# SD.net
KiCad netlist of a schematic drawn in Altium Designer
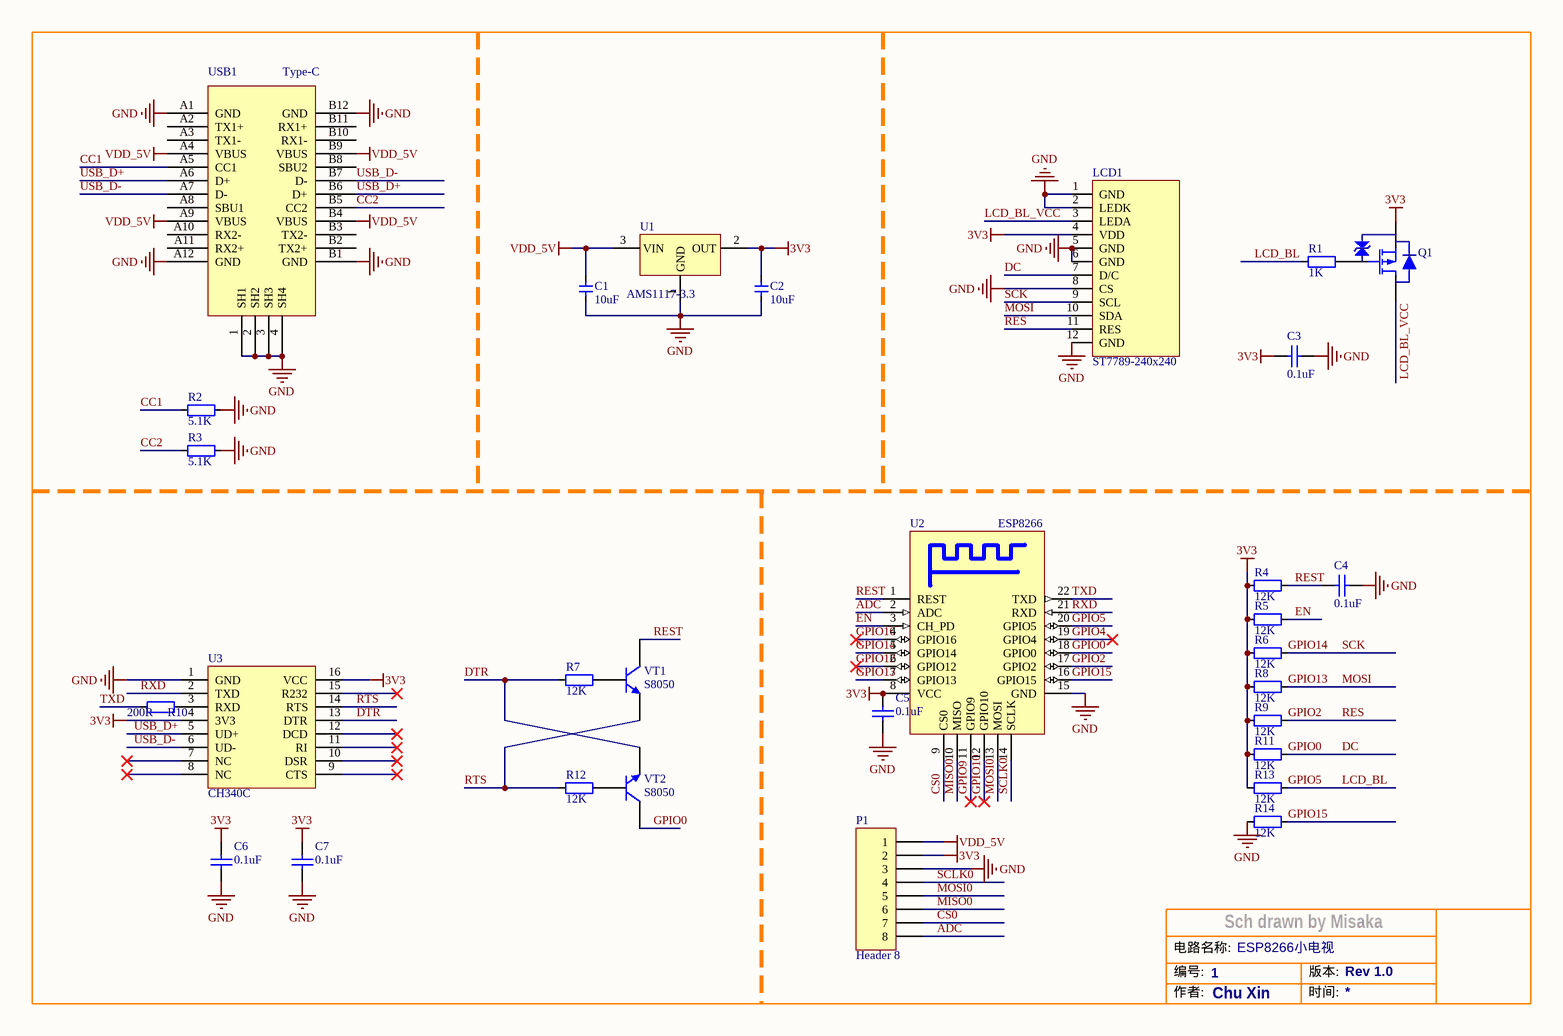
[diagram p0: SD²原理图.SchDoc]

(export (version "E")
  (design (tool "Eeschema 10.0.6"))
  (components
    (comp (ref "C1")
      (value "10uF")
      (footprint "C_0603")
      (description "Capacitor")
      (libsource (lib "MyPcbLib") (part "电容-0402"))
    )
    (comp (ref "C2")
      (value "10uF")
      (footprint "C_0603")
      (description "Capacitor")
      (libsource (lib "MyPcbLib") (part "电容-0402"))
    )
    (comp (ref "C3")
      (value "0.1uF")
      (footprint "C_0603")
      (description "Capacitor")
      (fields (field (name "PUBLISHER") "Altium Limited"))
      (libsource (lib "Miscellaneous Devices") (part "Cap"))
    )
    (comp (ref "C4")
      (value "0.1uF")
      (footprint "C_0603")
      (description "Capacitor")
      (fields (field (name "PUBLISHER") "Altium Limited"))
      (libsource (lib "Miscellaneous Devices") (part "Cap"))
    )
    (comp (ref "C5")
      (value "0.1uF")
      (footprint "C_0603")
      (description "Capacitor")
      (fields (field (name "PUBLISHER") "Altium Limited"))
      (libsource (lib "Miscellaneous Devices") (part "Cap"))
    )
    (comp (ref "C6")
      (value "0.1uF")
      (footprint "C_0603")
      (description "Capacitor")
      (fields (field (name "PUBLISHER") "Altium Limited"))
      (libsource (lib "Miscellaneous Devices") (part "Cap"))
    )
    (comp (ref "C7")
      (value "0.1uF")
      (footprint "C_0603")
      (description "Capacitor")
      (fields (field (name "PUBLISHER") "Altium Limited"))
      (libsource (lib "Miscellaneous Devices") (part "Cap"))
    )
    (comp (ref "LCD1")
      (value "ST7789-240x240")
      (footprint "LCD-240X240-12P")
      (description "显示屏")
      (libsource (lib "mLib") (part "LCD-240x240"))
    )
    (comp (ref "P1")
      (value "Header 8")
      (footprint "FFC_0.5_8")
      (description "Header, 8-Pin")
      (fields (field (name "PUBLISHER") "Altium Limited"))
      (libsource (lib "Miscellaneous Connectors") (part "Header 8"))
    )
    (comp (ref "Q1")
      (value "AO3415A")
      (footprint "SOT-23-y")
      (description "MOSFET")
      (fields (field (name "PUBLISHER") "Altium Limited"))
      (libsource (lib "MyPcbLib") (part "AO3415A"))
    )
    (comp (ref "R1")
      (value "1K")
      (footprint "R_0603")
      (description "Resistor")
      (libsource (lib "") (part "电阻-0402_1"))
    )
    (comp (ref "R2")
      (value "5.1K")
      (footprint "R_0603")
      (description "Resistor")
      (libsource (lib "MyPcbLib") (part "电阻-0402"))
    )
    (comp (ref "R3")
      (value "5.1K")
      (footprint "R_0603")
      (description "Resistor")
      (libsource (lib "MyPcbLib") (part "电阻-0402"))
    )
    (comp (ref "R4")
      (value "12K")
      (footprint "R_0603")
      (description "Resistor")
      (libsource (lib "MyPcbLib") (part "电阻-0402"))
    )
    (comp (ref "R5")
      (value "12K")
      (footprint "R_0603")
      (description "Resistor")
      (libsource (lib "MyPcbLib") (part "电阻-0402"))
    )
    (comp (ref "R6")
      (value "12K")
      (footprint "R_0603")
      (description "Resistor")
      (libsource (lib "MyPcbLib") (part "电阻-0402"))
    )
    (comp (ref "R7")
      (value "12K")
      (footprint "R_0603")
      (description "Resistor")
      (libsource (lib "MyPcbLib") (part "电阻-0402"))
    )
    (comp (ref "R8")
      (value "12K")
      (footprint "R_0603")
      (description "Resistor")
      (libsource (lib "MyPcbLib") (part "电阻-0402"))
    )
    (comp (ref "R9")
      (value "12K")
      (footprint "R_0603")
      (description "Resistor")
      (libsource (lib "MyPcbLib") (part "电阻-0402"))
    )
    (comp (ref "R10")
      (value "200R")
      (footprint "R_0603")
      (description "Resistor")
      (libsource (lib "") (part "电阻-0402_2"))
    )
    (comp (ref "R11")
      (value "12K")
      (footprint "R_0603")
      (description "Resistor")
      (libsource (lib "MyPcbLib") (part "电阻-0402"))
    )
    (comp (ref "R12")
      (value "12K")
      (footprint "R_0603")
      (description "Resistor")
      (libsource (lib "MyPcbLib") (part "电阻-0402"))
    )
    (comp (ref "R13")
      (value "12K")
      (footprint "R_0603")
      (description "Resistor")
      (libsource (lib "MyPcbLib") (part "电阻-0402"))
    )
    (comp (ref "R14")
      (value "12K")
      (footprint "R_0603")
      (description "Resistor")
      (libsource (lib "MyPcbLib") (part "电阻-0402"))
    )
    (comp (ref "U1") (value "AMS1117-3.3") (footprint "SOT223_y") (libsource (lib "数控电源") (part "LM317M")))
    (comp (ref "U2") (value "ESP8266") (footprint "8266") (libsource (lib "Misaka") (part "ESP8266")))
    (comp (ref "U3") (value "CH340C") (footprint "SOP16N_N") (libsource (lib "Misaka") (part "CH340C")))
    (comp (ref "USB1")
      (value "Type-C")
      (footprint "Misaka:Type-C-TOP")
      (libsource (lib "MyPcbLib") (part "USB-Type-C-TOP"))
    )
    (comp (ref "VT1")
      (value "S8050")
      (footprint "SOT-23-y")
      (description "Surface mount NPN transistor, package SOT-23")
      (libsource (lib "MyPcbLib") (part "SMT_TRIODE_NPN"))
    )
    (comp (ref "VT2")
      (value "S8050")
      (footprint "SOT-23-y")
      (description "Surface mount NPN transistor, package SOT-23")
      (libsource (lib "MyPcbLib") (part "SMT_TRIODE_NPN"))
    )
  )
  (nets
    (net (code "1") (name "/ADC") (class "Default")
      (node (ref "P1") (pin "8") (pinfunction "8_8") (pintype "passive"))
      (node (ref "U2") (pin "2") (pinfunction "ADC_2") (pintype "input"))
    )
    (net (code "2") (name "/CC1") (class "Default")
      (node (ref "R2") (pin "1") (pinfunction "1_1") (pintype "passive"))
      (node (ref "USB1") (pin "A5") (pinfunction "CC1_A5") (pintype "passive"))
    )
    (net (code "3") (name "/CC2") (class "Default")
      (node (ref "R3") (pin "1") (pinfunction "1_1") (pintype "passive"))
      (node (ref "USB1") (pin "B5") (pinfunction "CC2_B5") (pintype "passive"))
    )
    (net (code "4") (name "/CS0") (class "Default")
      (node (ref "P1") (pin "7") (pinfunction "7_7") (pintype "passive"))
      (node (ref "U2") (pin "9") (pinfunction "CS0_9") (pintype "passive"))
    )
    (net (code "5") (name "/DC") (class "Default")
      (node (ref "LCD1") (pin "7") (pinfunction "D/C_7") (pintype "passive"))
      (node (ref "R11") (pin "2") (pinfunction "2_2") (pintype "passive"))
      (node (ref "U2") (pin "18") (pinfunction "GPIO0_18") (pintype "bidirectional"))
      (node (ref "VT2") (pin "3") (pinfunction "C_3") (pintype "passive"))
    )
    (net (code "6") (name "/DTR") (class "Default")
      (node (ref "R7") (pin "1") (pinfunction "1_1") (pintype "passive"))
      (node (ref "U3") (pin "13") (pinfunction "DTR_13") (pintype "passive"))
      (node (ref "VT2") (pin "2") (pinfunction "E_2") (pintype "passive"))
    )
    (net (code "7") (name "/EN") (class "Default")
      (node (ref "R5") (pin "2") (pinfunction "2_2") (pintype "passive"))
      (node (ref "U2") (pin "3") (pinfunction "CH_PD_3") (pintype "input"))
    )
    (net (code "8") (name "/GPIO2") (class "Default")
      (node (ref "LCD1") (pin "11") (pinfunction "RES_11") (pintype "passive"))
      (node (ref "R9") (pin "2") (pinfunction "2_2") (pintype "passive"))
      (node (ref "U2") (pin "17") (pinfunction "GPIO2_17") (pintype "bidirectional"))
    )
    (net (code "9") (name "/GPIO4") (class "Default")
      (node (ref "U2") (pin "19") (pinfunction "GPIO4_19") (pintype "bidirectional+no_connect"))
    )
    (net (code "10") (name "/GPIO5") (class "Default")
      (node (ref "R1") (pin "1") (pinfunction "1_1") (pintype "passive"))
      (node (ref "R13") (pin "2") (pinfunction "2_2") (pintype "passive"))
      (node (ref "U2") (pin "20") (pinfunction "GPIO5_20") (pintype "bidirectional"))
    )
    (net (code "11") (name "/GPIO9") (class "Default")
      (node (ref "U2") (pin "11") (pinfunction "GPIO9_11") (pintype "passive+no_connect"))
    )
    (net (code "12") (name "/GPIO10") (class "Default")
      (node (ref "U2") (pin "12") (pinfunction "GPIO10_12") (pintype "passive+no_connect"))
    )
    (net (code "13") (name "/GPIO12") (class "Default")
      (node (ref "U2") (pin "6") (pinfunction "GPIO12_6") (pintype "bidirectional+no_connect"))
    )
    (net (code "14") (name "/GPIO13") (class "Default")
      (node (ref "LCD1") (pin "10") (pinfunction "SDA_10") (pintype "passive"))
      (node (ref "R8") (pin "2") (pinfunction "2_2") (pintype "passive"))
      (node (ref "U2") (pin "7") (pinfunction "GPIO13_7") (pintype "bidirectional"))
    )
    (net (code "15") (name "/GPIO14") (class "Default")
      (node (ref "LCD1") (pin "9") (pinfunction "SCL_9") (pintype "passive"))
      (node (ref "R6") (pin "2") (pinfunction "2_2") (pintype "passive"))
      (node (ref "U2") (pin "5") (pinfunction "GPIO14_5") (pintype "bidirectional"))
    )
    (net (code "16") (name "/GPIO15") (class "Default")
      (node (ref "R14") (pin "2") (pinfunction "2_2") (pintype "passive"))
      (node (ref "U2") (pin "16") (pinfunction "GPIO15_16") (pintype "bidirectional"))
    )
    (net (code "17") (name "/GPIO16") (class "Default")
      (node (ref "U2") (pin "4") (pinfunction "GPIO16_4") (pintype "bidirectional+no_connect"))
    )
    (net (code "18") (name "/LCD_BL_VCC") (class "Default")
      (node (ref "LCD1") (pin "3") (pinfunction "LEDA_3") (pintype "passive"))
      (node (ref "Q1") (pin "3") (pinfunction "D_3") (pintype "passive"))
    )
    (net (code "19") (name "/MISO0") (class "Default")
      (node (ref "P1") (pin "6") (pinfunction "6_6") (pintype "passive"))
      (node (ref "U2") (pin "10") (pinfunction "MISO_10") (pintype "passive"))
    )
    (net (code "20") (name "/MOSI0") (class "Default")
      (node (ref "P1") (pin "5") (pinfunction "5_5") (pintype "passive"))
      (node (ref "U2") (pin "13") (pinfunction "MOSI_13") (pintype "passive"))
    )
    (net (code "21") (name "/REST") (class "Default")
      (node (ref "C4") (pin "2") (pinfunction "2_2") (pintype "passive"))
      (node (ref "R4") (pin "2") (pinfunction "2_2") (pintype "passive"))
      (node (ref "U2") (pin "1") (pinfunction "REST_1") (pintype "passive"))
      (node (ref "VT1") (pin "3") (pinfunction "C_3") (pintype "passive"))
    )
    (net (code "22") (name "/RTS") (class "Default")
      (node (ref "R12") (pin "1") (pinfunction "1_1") (pintype "passive"))
      (node (ref "U3") (pin "14") (pinfunction "RTS_14") (pintype "passive"))
      (node (ref "VT1") (pin "2") (pinfunction "E_2") (pintype "passive"))
    )
    (net (code "23") (name "/RXD") (class "Default")
      (node (ref "U2") (pin "21") (pinfunction "RXD_21") (pintype "input"))
      (node (ref "U3") (pin "2") (pinfunction "TXD_2") (pintype "passive"))
    )
    (net (code "24") (name "/SCLK0") (class "Default")
      (node (ref "P1") (pin "4") (pinfunction "4_4") (pintype "passive"))
      (node (ref "U2") (pin "14") (pinfunction "SCLK_14") (pintype "passive"))
    )
    (net (code "25") (name "/TXD") (class "Default")
      (node (ref "R10") (pin "2") (pinfunction "2_2") (pintype "passive"))
      (node (ref "U2") (pin "22") (pinfunction "TXD_22") (pintype "output"))
    )
    (net (code "26") (name "/USB_D+") (class "Default")
      (node (ref "U3") (pin "5") (pinfunction "UD+_5") (pintype "passive"))
      (node (ref "USB1") (pin "A6") (pinfunction "D+_A6") (pintype "passive"))
      (node (ref "USB1") (pin "B6") (pinfunction "D+_B6") (pintype "passive"))
    )
    (net (code "27") (name "/USB_D-") (class "Default")
      (node (ref "U3") (pin "6") (pinfunction "UD-_6") (pintype "passive"))
      (node (ref "USB1") (pin "A7") (pinfunction "D-_A7") (pintype "passive"))
      (node (ref "USB1") (pin "B7") (pinfunction "D-_B7") (pintype "passive"))
    )
    (net (code "28") (name "3V3") (class "Default")
      (node (ref "C2") (pin "2") (pinfunction "2_2") (pintype "passive"))
      (node (ref "C3") (pin "2") (pinfunction "2_2") (pintype "passive"))
      (node (ref "C5") (pin "2") (pinfunction "2_2") (pintype "passive"))
      (node (ref "C6") (pin "2") (pinfunction "2_2") (pintype "passive"))
      (node (ref "C7") (pin "2") (pinfunction "2_2") (pintype "passive"))
      (node (ref "LCD1") (pin "4") (pinfunction "VDD_4") (pintype "passive"))
      (node (ref "P1") (pin "2") (pinfunction "2_2") (pintype "passive"))
      (node (ref "Q1") (pin "2") (pinfunction "S_2") (pintype "passive"))
      (node (ref "R11") (pin "1") (pinfunction "1_1") (pintype "passive"))
      (node (ref "R13") (pin "1") (pinfunction "1_1") (pintype "passive"))
      (node (ref "R4") (pin "1") (pinfunction "1_1") (pintype "passive"))
      (node (ref "R5") (pin "1") (pinfunction "1_1") (pintype "passive"))
      (node (ref "R6") (pin "1") (pinfunction "1_1") (pintype "passive"))
      (node (ref "R8") (pin "1") (pinfunction "1_1") (pintype "passive"))
      (node (ref "R9") (pin "1") (pinfunction "1_1") (pintype "passive"))
      (node (ref "U1") (pin "2") (pinfunction "OUT_2") (pintype "passive"))
      (node (ref "U2") (pin "8") (pinfunction "VCC_8") (pintype "power_in"))
      (node (ref "U3") (pin "16") (pinfunction "VCC_16") (pintype "passive"))
      (node (ref "U3") (pin "4") (pinfunction "3V3_4") (pintype "passive"))
    )
    (net (code "29") (name "GND") (class "Default")
      (node (ref "C1") (pin "1") (pinfunction "1_1") (pintype "passive"))
      (node (ref "C2") (pin "1") (pinfunction "1_1") (pintype "passive"))
      (node (ref "C3") (pin "1") (pinfunction "1_1") (pintype "passive"))
      (node (ref "C4") (pin "1") (pinfunction "1_1") (pintype "passive"))
      (node (ref "C5") (pin "1") (pinfunction "1_1") (pintype "passive"))
      (node (ref "C6") (pin "1") (pinfunction "1_1") (pintype "passive"))
      (node (ref "C7") (pin "1") (pinfunction "1_1") (pintype "passive"))
      (node (ref "LCD1") (pin "1") (pinfunction "GND_1") (pintype "passive"))
      (node (ref "LCD1") (pin "12") (pinfunction "GND_12") (pintype "passive"))
      (node (ref "LCD1") (pin "2") (pinfunction "LEDK_2") (pintype "passive"))
      (node (ref "LCD1") (pin "5") (pinfunction "GND_5") (pintype "passive"))
      (node (ref "LCD1") (pin "6") (pinfunction "GND_6") (pintype "passive"))
      (node (ref "LCD1") (pin "8") (pinfunction "CS_8") (pintype "passive"))
      (node (ref "P1") (pin "3") (pinfunction "3_3") (pintype "passive"))
      (node (ref "R14") (pin "1") (pinfunction "1_1") (pintype "passive"))
      (node (ref "R2") (pin "2") (pinfunction "2_2") (pintype "passive"))
      (node (ref "R3") (pin "2") (pinfunction "2_2") (pintype "passive"))
      (node (ref "U1") (pin "1") (pinfunction "GND_1") (pintype "passive"))
      (node (ref "U2") (pin "15") (pinfunction "GND_15") (pintype "power_in"))
      (node (ref "U3") (pin "1") (pinfunction "GND_1") (pintype "passive"))
      (node (ref "USB1") (pin "1") (pinfunction "SH1_1") (pintype "passive"))
      (node (ref "USB1") (pin "2") (pinfunction "SH2_2") (pintype "passive"))
      (node (ref "USB1") (pin "3") (pinfunction "SH3_3") (pintype "passive"))
      (node (ref "USB1") (pin "4") (pinfunction "SH4_4") (pintype "passive"))
      (node (ref "USB1") (pin "A1") (pinfunction "GND_A1") (pintype "passive"))
      (node (ref "USB1") (pin "A12") (pinfunction "GND_A12") (pintype "passive"))
      (node (ref "USB1") (pin "B1") (pinfunction "GND_B1") (pintype "passive"))
      (node (ref "USB1") (pin "B12") (pinfunction "GND_B12") (pintype "passive"))
    )
    (net (code "30") (name "Net-(Q1-G)") (class "Default")
      (node (ref "Q1") (pin "1") (pinfunction "G_1") (pintype "passive"))
      (node (ref "R1") (pin "2") (pinfunction "2_2") (pintype "passive"))
    )
    (net (code "31") (name "Net-(U3-RXD)") (class "Default")
      (node (ref "R10") (pin "1") (pinfunction "1_1") (pintype "passive"))
      (node (ref "U3") (pin "3") (pinfunction "RXD_3") (pintype "passive"))
    )
    (net (code "32") (name "Net-(VT1-B)") (class "Default")
      (node (ref "R7") (pin "2") (pinfunction "2_2") (pintype "passive"))
      (node (ref "VT1") (pin "1") (pinfunction "B_1") (pintype "passive"))
    )
    (net (code "33") (name "Net-(VT2-B)") (class "Default")
      (node (ref "R12") (pin "2") (pinfunction "2_2") (pintype "passive"))
      (node (ref "VT2") (pin "1") (pinfunction "B_1") (pintype "passive"))
    )
    (net (code "34") (name "VDD_5V") (class "Default")
      (node (ref "C1") (pin "2") (pinfunction "2_2") (pintype "passive"))
      (node (ref "P1") (pin "1") (pinfunction "1_1") (pintype "passive"))
      (node (ref "U1") (pin "3") (pinfunction "VIN_3") (pintype "passive"))
      (node (ref "USB1") (pin "A4") (pinfunction "VBUS_A4") (pintype "passive"))
      (node (ref "USB1") (pin "A9") (pinfunction "VBUS_A9") (pintype "passive"))
      (node (ref "USB1") (pin "B4") (pinfunction "VBUS_B4") (pintype "passive"))
      (node (ref "USB1") (pin "B9") (pinfunction "VBUS_B9") (pintype "passive"))
    )
    (net (code "35") (name "unconnected-(U3-CTS-Pad9)") (class "Default")
      (node (ref "U3") (pin "9") (pinfunction "CTS_9") (pintype "passive+no_connect"))
    )
    (net (code "36") (name "unconnected-(U3-DCD-Pad12)") (class "Default")
      (node (ref "U3") (pin "12") (pinfunction "DCD_12") (pintype "passive+no_connect"))
    )
    (net (code "37") (name "unconnected-(U3-DSR-Pad10)") (class "Default")
      (node (ref "U3") (pin "10") (pinfunction "DSR_10") (pintype "passive+no_connect"))
    )
    (net (code "38") (name "unconnected-(U3-NC-Pad7)") (class "Default")
      (node (ref "U3") (pin "7") (pinfunction "NC_7") (pintype "passive+no_connect"))
    )
    (net (code "39") (name "unconnected-(U3-NC-Pad8)") (class "Default")
      (node (ref "U3") (pin "8") (pinfunction "NC_8") (pintype "passive+no_connect"))
    )
    (net (code "40") (name "unconnected-(U3-R232-Pad15)") (class "Default")
      (node (ref "U3") (pin "15") (pinfunction "R232_15") (pintype "passive+no_connect"))
    )
    (net (code "41") (name "unconnected-(U3-RI-Pad11)") (class "Default")
      (node (ref "U3") (pin "11") (pinfunction "RI_11") (pintype "passive+no_connect"))
    )
    (net (code "42") (name "unconnected-(USB1-RX1+-PadB11)") (class "Default")
      (node (ref "USB1") (pin "B11") (pinfunction "RX1+_B11") (pintype "passive"))
    )
    (net (code "43") (name "unconnected-(USB1-RX1--PadB10)") (class "Default")
      (node (ref "USB1") (pin "B10") (pinfunction "RX1-_B10") (pintype "passive"))
    )
    (net (code "44") (name "unconnected-(USB1-RX2+-PadA11)") (class "Default")
      (node (ref "USB1") (pin "A11") (pinfunction "RX2+_A11") (pintype "passive"))
    )
    (net (code "45") (name "unconnected-(USB1-RX2--PadA10)") (class "Default")
      (node (ref "USB1") (pin "A10") (pinfunction "RX2-_A10") (pintype "passive"))
    )
    (net (code "46") (name "unconnected-(USB1-SBU1-PadA8)") (class "Default")
      (node (ref "USB1") (pin "A8") (pinfunction "SBU1_A8") (pintype "passive"))
    )
    (net (code "47") (name "unconnected-(USB1-SBU2-PadB8)") (class "Default")
      (node (ref "USB1") (pin "B8") (pinfunction "SBU2_B8") (pintype "passive"))
    )
    (net (code "48") (name "unconnected-(USB1-TX1+-PadA2)") (class "Default")
      (node (ref "USB1") (pin "A2") (pinfunction "TX1+_A2") (pintype "passive"))
    )
    (net (code "49") (name "unconnected-(USB1-TX1--PadA3)") (class "Default")
      (node (ref "USB1") (pin "A3") (pinfunction "TX1-_A3") (pintype "passive"))
    )
    (net (code "50") (name "unconnected-(USB1-TX2+-PadB2)") (class "Default")
      (node (ref "USB1") (pin "B2") (pinfunction "TX2+_B2") (pintype "passive"))
    )
    (net (code "51") (name "unconnected-(USB1-TX2--PadB3)") (class "Default")
      (node (ref "USB1") (pin "B3") (pinfunction "TX2-_B3") (pintype "passive"))
    )
  )
)
